# modulator.net
KiCad netlist of a schematic drawn in EAGLE
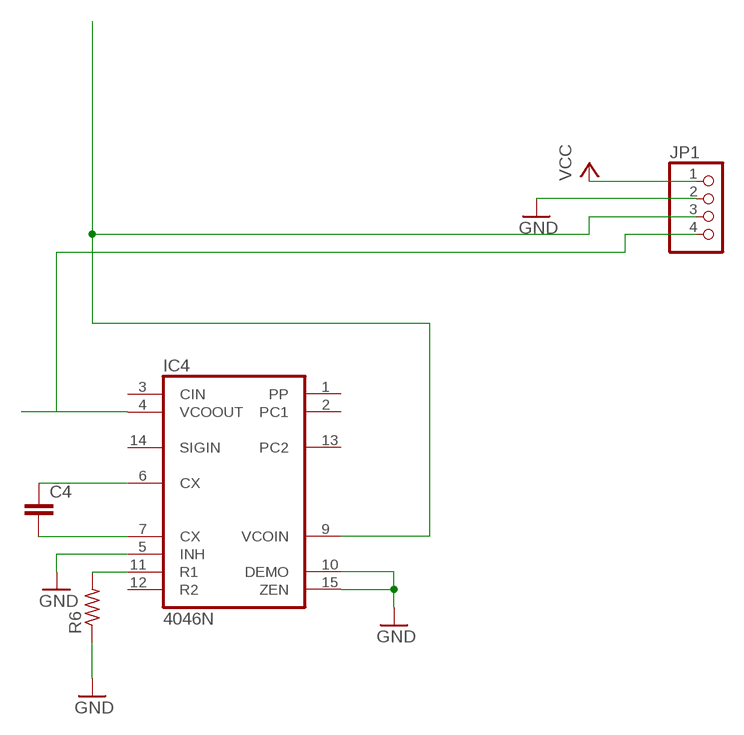
[diagram p0: schematic, sheet 1]

(export (version "E")
  (design (tool "Eeschema 10.0.6"))
  (components
    (comp (ref "C4")
      (value "C2.5/2")
      (footprint "eagle-import:C2.5-2")
      (libsource (lib "eagle-import") (part "C2.5/2"))
    )
    (comp (ref "IC4")
      (value "4046N")
      (footprint "eagle-import:DIL16")
      (libsource (lib "eagle-import") (part "4046N"))
    )
    (comp (ref "JP1")
      (value "PINHD-1X4")
      (footprint "eagle-import:1X04")
      (libsource (lib "eagle-import") (part "PINHD-1X4"))
    )
    (comp (ref "R6")
      (value "R-US_0204/7")
      (footprint "eagle-import:0204_7")
      (libsource (lib "eagle-import") (part "R-US_0204/7"))
    )
  )
  (nets
    (net (code "1") (name "GND") (class "Default")
      (node (ref "IC4") (pin "10") (pinfunction "DEMO_10") (pintype "output"))
      (node (ref "IC4") (pin "15") (pinfunction "ZEN_15") (pintype "input"))
      (node (ref "IC4") (pin "5") (pinfunction "INH_5") (pintype "input"))
      (node (ref "JP1") (pin "2") (pinfunction "2_2") (pintype "passive"))
      (node (ref "R6") (pin "1") (pinfunction "1_1") (pintype "passive"))
    )
    (net (code "2") (name "Net-(C4-Pad1)") (class "Default")
      (node (ref "C4") (pin "1") (pinfunction "1_1") (pintype "passive"))
      (node (ref "IC4") (pin "6") (pinfunction "CX_6") (pintype "input"))
    )
    (net (code "3") (name "Net-(C4-Pad2)") (class "Default")
      (node (ref "C4") (pin "2") (pinfunction "2_2") (pintype "passive"))
      (node (ref "IC4") (pin "7") (pinfunction "CX_7") (pintype "input"))
    )
    (net (code "4") (name "Net-(IC4A-R1)") (class "Default")
      (node (ref "IC4") (pin "11") (pinfunction "R1_11") (pintype "input"))
      (node (ref "R6") (pin "2") (pinfunction "2_2") (pintype "passive"))
    )
    (net (code "5") (name "Net-(IC4A-VCOIN)") (class "Default")
      (node (ref "IC4") (pin "9") (pinfunction "VCOIN_9") (pintype "input"))
      (node (ref "JP1") (pin "3") (pinfunction "3_3") (pintype "passive"))
    )
    (net (code "6") (name "Net-(IC4A-VCOOUT)") (class "Default")
      (node (ref "IC4") (pin "4") (pinfunction "VCOOUT_4") (pintype "output"))
      (node (ref "JP1") (pin "4") (pinfunction "4_4") (pintype "passive"))
    )
    (net (code "7") (name "VCC") (class "Default")
      (node (ref "JP1") (pin "1") (pinfunction "1_1") (pintype "passive"))
    )
    (net (code "8") (name "unconnected-(IC4A-CIN-Pad3)") (class "Default")
      (node (ref "IC4") (pin "3") (pinfunction "CIN_3") (pintype "input"))
    )
    (net (code "9") (name "unconnected-(IC4A-PC1-Pad2)") (class "Default")
      (node (ref "IC4") (pin "2") (pinfunction "PC1_2") (pintype "output"))
    )
    (net (code "10") (name "unconnected-(IC4A-PC2-Pad13)") (class "Default")
      (node (ref "IC4") (pin "13") (pinfunction "PC2_13") (pintype "output"))
    )
    (net (code "11") (name "unconnected-(IC4A-PP-Pad1)") (class "Default")
      (node (ref "IC4") (pin "1") (pinfunction "PP_1") (pintype "output"))
    )
    (net (code "12") (name "unconnected-(IC4A-R2-Pad12)") (class "Default")
      (node (ref "IC4") (pin "12") (pinfunction "R2_12") (pintype "input"))
    )
    (net (code "13") (name "unconnected-(IC4A-SIGIN-Pad14)") (class "Default")
      (node (ref "IC4") (pin "14") (pinfunction "SIGIN_14") (pintype "input"))
    )
  )
)
